# rgb_breakout.net
KiCad netlist of a schematic drawn in EAGLE
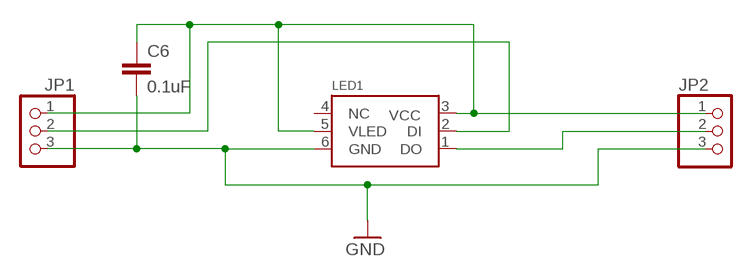
[diagram p0: schematic, sheet 1]

(export (version "E")
  (design (tool "Eeschema 10.0.6"))
  (components
    (comp (ref "C6")
      (value "0.1uF")
      (footprint "eagle-import:C0805")
      (libsource (lib "eagle-import") (part "C-EUC0805"))
    )
    (comp (ref "JP1")
      (value "PINHD-1X3")
      (footprint "eagle-import:1X03")
      (libsource (lib "eagle-import") (part "PINHD-1X3"))
    )
    (comp (ref "JP2")
      (value "PINHD-1X3")
      (footprint "eagle-import:1X03")
      (libsource (lib "eagle-import") (part "PINHD-1X3"))
    )
    (comp (ref "LED1")
      (value "5050WS2811W")
      (footprint "eagle-import:RGBLED5050W")
      (libsource (lib "eagle-import") (part "5050WS2811W"))
    )
  )
  (nets
    (net (code "1") (name "GND") (class "Default")
      (node (ref "C6") (pin "2") (pinfunction "2_2") (pintype "passive"))
      (node (ref "JP1") (pin "3") (pinfunction "3_3") (pintype "passive"))
      (node (ref "JP2") (pin "3") (pinfunction "3_3") (pintype "passive"))
      (node (ref "LED1") (pin "6") (pinfunction "GND_6") (pintype "bidirectional"))
    )
    (net (code "2") (name "Net-(LED1-DI)") (class "Default")
      (node (ref "JP1") (pin "2") (pinfunction "2_2") (pintype "passive"))
      (node (ref "LED1") (pin "2") (pinfunction "DI_2") (pintype "bidirectional"))
    )
    (net (code "3") (name "Net-(LED1-DO)") (class "Default")
      (node (ref "JP2") (pin "2") (pinfunction "2_2") (pintype "passive"))
      (node (ref "LED1") (pin "1") (pinfunction "DO_1") (pintype "bidirectional"))
    )
    (net (code "4") (name "Net-(LED1-VCC)") (class "Default")
      (node (ref "C6") (pin "1") (pinfunction "1_1") (pintype "passive"))
      (node (ref "JP1") (pin "1") (pinfunction "1_1") (pintype "passive"))
      (node (ref "JP2") (pin "1") (pinfunction "1_1") (pintype "passive"))
      (node (ref "LED1") (pin "3") (pinfunction "VCC_3") (pintype "bidirectional"))
      (node (ref "LED1") (pin "5") (pinfunction "VLED_5") (pintype "bidirectional"))
    )
    (net (code "5") (name "unconnected-(LED1-NC-Pad4)") (class "Default")
      (node (ref "LED1") (pin "4") (pinfunction "NC_4") (pintype "bidirectional"))
    )
  )
)
